# plotter_control.net
KiCad netlist of a schematic drawn in EAGLE
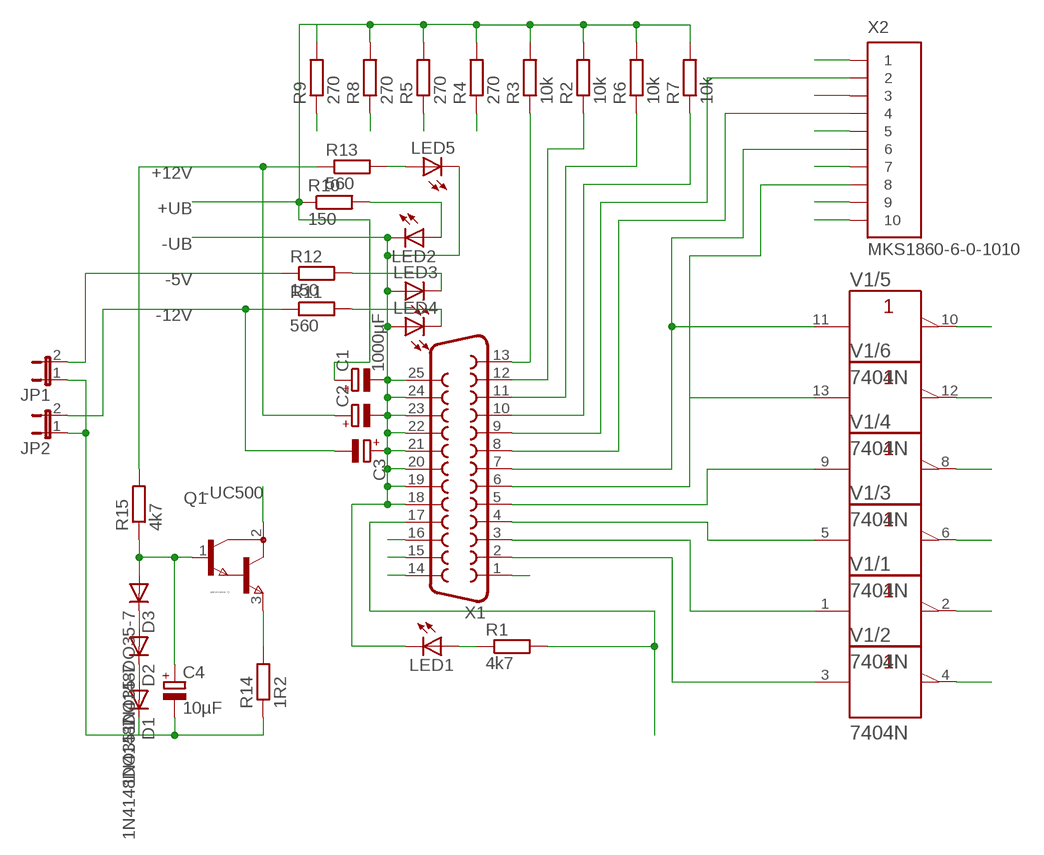
[diagram p0: schematic, sheet 1]

(export (version "E")
  (design (tool "Eeschema 10.0.6"))
  (components
    (comp (ref "C1")
      (value "1000µF")
      (footprint "eagle-import:E5-8,5")
      (libsource (lib "eagle-import") (part "CPOL-EUE5-8.5"))
    )
    (comp (ref "C2")
      (value "CPOL-EUE5-8.5")
      (footprint "eagle-import:E5-8,5")
      (libsource (lib "eagle-import") (part "CPOL-EUE5-8.5"))
    )
    (comp (ref "C3")
      (value "CPOL-EUE5-8.5")
      (footprint "eagle-import:E5-8,5")
      (libsource (lib "eagle-import") (part "CPOL-EUE5-8.5"))
    )
    (comp (ref "C4")
      (value "10µF")
      (footprint "eagle-import:E2,5-5")
      (libsource (lib "eagle-import") (part "CPOL-EUE2.5-5"))
    )
    (comp (ref "D1")
      (value "1N4148DO35-7")
      (footprint "eagle-import:DO35-7")
      (libsource (lib "eagle-import") (part "1N4148DO35-7"))
    )
    (comp (ref "D2")
      (value "1N4148DO35-7")
      (footprint "eagle-import:DO35-7")
      (libsource (lib "eagle-import") (part "1N4148DO35-7"))
    )
    (comp (ref "D3")
      (value "1N4148DO35-7")
      (footprint "eagle-import:DO35-7")
      (libsource (lib "eagle-import") (part "1N4148DO35-7"))
    )
    (comp (ref "JP1")
      (value "JP1E")
      (footprint "eagle-import:JP1")
      (libsource (lib "eagle-import") (part "JP1E"))
    )
    (comp (ref "JP2")
      (value "JP1E")
      (footprint "eagle-import:JP1")
      (libsource (lib "eagle-import") (part "JP1E"))
    )
    (comp (ref "LED1")
      (value "LED3MM")
      (footprint "eagle-import:LED3MM")
      (libsource (lib "eagle-import") (part "LED3MM"))
    )
    (comp (ref "LED2")
      (value "LED3MM")
      (footprint "eagle-import:LED3MM")
      (libsource (lib "eagle-import") (part "LED3MM"))
    )
    (comp (ref "LED3")
      (value "LED3MM")
      (footprint "eagle-import:LED3MM")
      (libsource (lib "eagle-import") (part "LED3MM"))
    )
    (comp (ref "LED4")
      (value "LED3MM")
      (footprint "eagle-import:LED3MM")
      (libsource (lib "eagle-import") (part "LED3MM"))
    )
    (comp (ref "LED5")
      (value "LED3MM")
      (footprint "eagle-import:LED3MM")
      (libsource (lib "eagle-import") (part "LED3MM"))
    )
    (comp (ref "Q1")
      (value "BD647")
      (footprint "eagle-import:TO220")
      (libsource (lib "eagle-import") (part "BD647"))
    )
    (comp (ref "R1")
      (value "4k7")
      (footprint "eagle-import:0204_7")
      (libsource (lib "eagle-import") (part "R-EU_0204/7"))
    )
    (comp (ref "R2")
      (value "10k")
      (footprint "eagle-import:0204_7")
      (libsource (lib "eagle-import") (part "R-EU_0204/7"))
    )
    (comp (ref "R3")
      (value "10k")
      (footprint "eagle-import:0204_7")
      (libsource (lib "eagle-import") (part "R-EU_0204/7"))
    )
    (comp (ref "R4")
      (value "270")
      (footprint "eagle-import:0204_7")
      (libsource (lib "eagle-import") (part "R-EU_0204/7"))
    )
    (comp (ref "R5")
      (value "270")
      (footprint "eagle-import:0204_7")
      (libsource (lib "eagle-import") (part "R-EU_0204/7"))
    )
    (comp (ref "R6")
      (value "10k")
      (footprint "eagle-import:0204_7")
      (libsource (lib "eagle-import") (part "R-EU_0204/7"))
    )
    (comp (ref "R7")
      (value "10k")
      (footprint "eagle-import:0204_7")
      (libsource (lib "eagle-import") (part "R-EU_0204/7"))
    )
    (comp (ref "R8")
      (value "270")
      (footprint "eagle-import:0204_7")
      (libsource (lib "eagle-import") (part "R-EU_0204/7"))
    )
    (comp (ref "R9")
      (value "270")
      (footprint "eagle-import:0204_7")
      (libsource (lib "eagle-import") (part "R-EU_0204/7"))
    )
    (comp (ref "R10")
      (value "150")
      (footprint "eagle-import:0207_15")
      (libsource (lib "eagle-import") (part "R-EU_0207/15"))
    )
    (comp (ref "R11")
      (value "560")
      (footprint "eagle-import:0204_7")
      (libsource (lib "eagle-import") (part "R-EU_0204/7"))
    )
    (comp (ref "R12")
      (value "150")
      (footprint "eagle-import:0207_10")
      (libsource (lib "eagle-import") (part "R-EU_0207/10"))
    )
    (comp (ref "R13")
      (value "560")
      (footprint "eagle-import:0204_7")
      (libsource (lib "eagle-import") (part "R-EU_0204/7"))
    )
    (comp (ref "R14")
      (value "1R2")
      (footprint "eagle-import:0204_7")
      (libsource (lib "eagle-import") (part "R-EU_0204/7"))
    )
    (comp (ref "R15")
      (value "4k7")
      (footprint "eagle-import:0204_7")
      (libsource (lib "eagle-import") (part "R-EU_0204/7"))
    )
    (comp (ref "V1")
      (value "7404N")
      (footprint "eagle-import:DIL14")
      (libsource (lib "eagle-import") (part "7404N"))
    )
    (comp (ref "X1")
      (value "F25HP")
      (footprint "eagle-import:F25HP")
      (libsource (lib "eagle-import") (part "F25HP"))
    )
    (comp (ref "X2")
      (value "MKS1860-6-0-1010")
      (footprint "eagle-import:MKS1860-6-0-1010")
      (libsource (lib "eagle-import") (part "MKS1860-6-0-1010"))
    )
  )
  (nets
    (net (code "1") (name "/+12V") (class "Default")
      (node (ref "C2") (pin "+") (pinfunction "+_+") (pintype "passive"))
      (node (ref "R13") (pin "1") (pinfunction "1_1") (pintype "passive"))
      (node (ref "R15") (pin "2") (pinfunction "2_2") (pintype "passive"))
    )
    (net (code "2") (name "/+UB") (class "Default")
      (node (ref "C1") (pin "+") (pinfunction "+_+") (pintype "passive"))
      (node (ref "R10") (pin "1") (pinfunction "1_1") (pintype "passive"))
      (node (ref "R2") (pin "2") (pinfunction "2_2") (pintype "passive"))
      (node (ref "R3") (pin "2") (pinfunction "2_2") (pintype "passive"))
      (node (ref "R4") (pin "2") (pinfunction "2_2") (pintype "passive"))
      (node (ref "R5") (pin "2") (pinfunction "2_2") (pintype "passive"))
      (node (ref "R6") (pin "2") (pinfunction "2_2") (pintype "passive"))
      (node (ref "R7") (pin "2") (pinfunction "2_2") (pintype "passive"))
      (node (ref "R8") (pin "2") (pinfunction "2_2") (pintype "passive"))
      (node (ref "R9") (pin "2") (pinfunction "2_2") (pintype "passive"))
    )
    (net (code "3") (name "/-5V") (class "Default")
      (node (ref "JP1") (pin "2") (pinfunction "2_2") (pintype "passive"))
      (node (ref "R12") (pin "1") (pinfunction "1_1") (pintype "passive"))
    )
    (net (code "4") (name "/-12V") (class "Default")
      (node (ref "C3") (pin "-") (pinfunction "-_-") (pintype "passive"))
      (node (ref "JP2") (pin "2") (pinfunction "2_2") (pintype "passive"))
      (node (ref "R11") (pin "1") (pinfunction "1_1") (pintype "passive"))
    )
    (net (code "5") (name "/-UB") (class "Default")
      (node (ref "C1") (pin "-") (pinfunction "-_-") (pintype "passive"))
      (node (ref "C2") (pin "-") (pinfunction "-_-") (pintype "passive"))
      (node (ref "C3") (pin "+") (pinfunction "+_+") (pintype "passive"))
      (node (ref "LED1") (pin "K") (pinfunction "C_K") (pintype "passive"))
      (node (ref "LED2") (pin "K") (pinfunction "C_K") (pintype "passive"))
      (node (ref "LED3") (pin "A") (pinfunction "A_A") (pintype "passive"))
      (node (ref "LED4") (pin "A") (pinfunction "A_A") (pintype "passive"))
      (node (ref "LED5") (pin "K") (pinfunction "C_K") (pintype "passive"))
      (node (ref "X1") (pin "18") (pinfunction "18_18") (pintype "passive"))
      (node (ref "X1") (pin "19") (pinfunction "19_19") (pintype "passive"))
      (node (ref "X1") (pin "20") (pinfunction "20_20") (pintype "passive"))
      (node (ref "X1") (pin "21") (pinfunction "21_21") (pintype "passive"))
      (node (ref "X1") (pin "22") (pinfunction "22_22") (pintype "passive"))
      (node (ref "X1") (pin "23") (pinfunction "23_23") (pintype "passive"))
      (node (ref "X1") (pin "24") (pinfunction "24_24") (pintype "passive"))
      (node (ref "X1") (pin "25") (pinfunction "25_25") (pintype "passive"))
      (node (ref "X2") (pin "1") (pinfunction "1_1") (pintype "input"))
      (node (ref "X2") (pin "10") (pinfunction "10_10") (pintype "input"))
    )
    (net (code "6") (name "/-UC500") (class "Default")
      (node (ref "Q1") (pin "2") (pinfunction "C_2") (pintype "passive"))
    )
    (net (code "7") (name "Net-(C4-Pad-)") (class "Default")
      (node (ref "C4") (pin "-") (pinfunction "-_-") (pintype "passive"))
      (node (ref "D1") (pin "C") (pinfunction "C_C") (pintype "passive"))
      (node (ref "JP1") (pin "1") (pinfunction "1_1") (pintype "passive"))
      (node (ref "JP2") (pin "1") (pinfunction "1_1") (pintype "passive"))
      (node (ref "R14") (pin "1") (pinfunction "1_1") (pintype "passive"))
    )
    (net (code "8") (name "Net-(D1-PadA)") (class "Default")
      (node (ref "D1") (pin "A") (pinfunction "A_A") (pintype "passive"))
      (node (ref "D2") (pin "C") (pinfunction "C_C") (pintype "passive"))
    )
    (net (code "9") (name "Net-(D2-PadA)") (class "Default")
      (node (ref "D2") (pin "A") (pinfunction "A_A") (pintype "passive"))
      (node (ref "D3") (pin "C") (pinfunction "C_C") (pintype "passive"))
    )
    (net (code "10") (name "Net-(LED1-PadA)") (class "Default")
      (node (ref "LED1") (pin "A") (pinfunction "A_A") (pintype "passive"))
      (node (ref "R1") (pin "1") (pinfunction "1_1") (pintype "passive"))
    )
    (net (code "11") (name "Net-(LED2-PadA)") (class "Default")
      (node (ref "LED2") (pin "A") (pinfunction "A_A") (pintype "passive"))
      (node (ref "R10") (pin "2") (pinfunction "2_2") (pintype "passive"))
    )
    (net (code "12") (name "Net-(LED3-C)") (class "Default")
      (node (ref "LED3") (pin "K") (pinfunction "C_K") (pintype "passive"))
      (node (ref "R12") (pin "2") (pinfunction "2_2") (pintype "passive"))
    )
    (net (code "13") (name "Net-(LED4-C)") (class "Default")
      (node (ref "LED4") (pin "K") (pinfunction "C_K") (pintype "passive"))
      (node (ref "R11") (pin "2") (pinfunction "2_2") (pintype "passive"))
    )
    (net (code "14") (name "Net-(LED5-PadA)") (class "Default")
      (node (ref "LED5") (pin "A") (pinfunction "A_A") (pintype "passive"))
      (node (ref "R13") (pin "2") (pinfunction "2_2") (pintype "passive"))
    )
    (net (code "15") (name "Net-(Q1-B)") (class "Default")
      (node (ref "C4") (pin "+") (pinfunction "+_+") (pintype "passive"))
      (node (ref "D3") (pin "A") (pinfunction "A_A") (pintype "passive"))
      (node (ref "Q1") (pin "1") (pinfunction "B_1") (pintype "passive"))
      (node (ref "R15") (pin "1") (pinfunction "1_1") (pintype "passive"))
    )
    (net (code "16") (name "Net-(Q1-E)") (class "Default")
      (node (ref "Q1") (pin "3") (pinfunction "E_3") (pintype "passive"))
      (node (ref "R14") (pin "2") (pinfunction "2_2") (pintype "passive"))
    )
    (net (code "17") (name "Net-(R1-Pad2)") (class "Default")
      (node (ref "R1") (pin "2") (pinfunction "2_2") (pintype "passive"))
      (node (ref "X1") (pin "17") (pinfunction "17_17") (pintype "passive"))
    )
    (net (code "18") (name "Net-(R2-Pad1)") (class "Default")
      (node (ref "R2") (pin "1") (pinfunction "1_1") (pintype "passive"))
      (node (ref "X1") (pin "12") (pinfunction "12_12") (pintype "passive"))
    )
    (net (code "19") (name "Net-(R3-Pad1)") (class "Default")
      (node (ref "R3") (pin "1") (pinfunction "1_1") (pintype "passive"))
      (node (ref "X1") (pin "13") (pinfunction "13_13") (pintype "passive"))
    )
    (net (code "20") (name "Net-(R6-Pad1)") (class "Default")
      (node (ref "R6") (pin "1") (pinfunction "1_1") (pintype "passive"))
      (node (ref "X1") (pin "11") (pinfunction "11_11") (pintype "passive"))
    )
    (net (code "21") (name "Net-(R7-Pad1)") (class "Default")
      (node (ref "R7") (pin "1") (pinfunction "1_1") (pintype "passive"))
      (node (ref "X1") (pin "10") (pinfunction "10_10") (pintype "passive"))
    )
    (net (code "22") (name "Net-(V1C-A)") (class "Default")
      (node (ref "V1") (pin "1") (pinfunction "A_1") (pintype "input"))
      (node (ref "X1") (pin "3") (pinfunction "3_3") (pintype "passive"))
    )
    (net (code "23") (name "Net-(V1D-A)") (class "Default")
      (node (ref "V1") (pin "3") (pinfunction "A_3") (pintype "input"))
      (node (ref "X1") (pin "2") (pinfunction "2_2") (pintype "passive"))
    )
    (net (code "24") (name "Net-(V1E-A)") (class "Default")
      (node (ref "V1") (pin "5") (pinfunction "A_5") (pintype "input"))
      (node (ref "X1") (pin "4") (pinfunction "4_4") (pintype "passive"))
    )
    (net (code "25") (name "Net-(V1F-A)") (class "Default")
      (node (ref "V1") (pin "9") (pinfunction "A_9") (pintype "input"))
      (node (ref "X1") (pin "5") (pinfunction "5_5") (pintype "passive"))
    )
    (net (code "26") (name "Net-(V1G-A)") (class "Default")
      (node (ref "V1") (pin "11") (pinfunction "A_11") (pintype "input"))
      (node (ref "X1") (pin "7") (pinfunction "7_7") (pintype "passive"))
      (node (ref "X2") (pin "6") (pinfunction "6_6") (pintype "input"))
    )
    (net (code "27") (name "Net-(V1H-A)") (class "Default")
      (node (ref "V1") (pin "13") (pinfunction "A_13") (pintype "input"))
      (node (ref "X1") (pin "6") (pinfunction "6_6") (pintype "passive"))
      (node (ref "X2") (pin "8") (pinfunction "8_8") (pintype "input"))
    )
    (net (code "28") (name "Net-(X1-Pad8)") (class "Default")
      (node (ref "X1") (pin "8") (pinfunction "8_8") (pintype "passive"))
      (node (ref "X2") (pin "4") (pinfunction "4_4") (pintype "input"))
    )
    (net (code "29") (name "Net-(X1-Pad9)") (class "Default")
      (node (ref "X1") (pin "9") (pinfunction "9_9") (pintype "passive"))
      (node (ref "X2") (pin "2") (pinfunction "2_2") (pintype "input"))
    )
    (net (code "30") (name "unconnected-(R4-Pad1)") (class "Default")
      (node (ref "R4") (pin "1") (pinfunction "1_1") (pintype "passive"))
    )
    (net (code "31") (name "unconnected-(R5-Pad1)") (class "Default")
      (node (ref "R5") (pin "1") (pinfunction "1_1") (pintype "passive"))
    )
    (net (code "32") (name "unconnected-(R8-Pad1)") (class "Default")
      (node (ref "R8") (pin "1") (pinfunction "1_1") (pintype "passive"))
    )
    (net (code "33") (name "unconnected-(R9-Pad1)") (class "Default")
      (node (ref "R9") (pin "1") (pinfunction "1_1") (pintype "passive"))
    )
    (net (code "34") (name "unconnected-(V1C-Y-Pad2)") (class "Default")
      (node (ref "V1") (pin "2") (pinfunction "Y_2") (pintype "output"))
    )
    (net (code "35") (name "unconnected-(V1D-Y-Pad4)") (class "Default")
      (node (ref "V1") (pin "4") (pinfunction "Y_4") (pintype "output"))
    )
    (net (code "36") (name "unconnected-(V1E-Y-Pad6)") (class "Default")
      (node (ref "V1") (pin "6") (pinfunction "Y_6") (pintype "output"))
    )
    (net (code "37") (name "unconnected-(V1F-Y-Pad8)") (class "Default")
      (node (ref "V1") (pin "8") (pinfunction "Y_8") (pintype "output"))
    )
    (net (code "38") (name "unconnected-(V1G-Y-Pad10)") (class "Default")
      (node (ref "V1") (pin "10") (pinfunction "Y_10") (pintype "output"))
    )
    (net (code "39") (name "unconnected-(V1H-Y-Pad12)") (class "Default")
      (node (ref "V1") (pin "12") (pinfunction "Y_12") (pintype "output"))
    )
    (net (code "40") (name "unconnected-(X1-Pad1)") (class "Default")
      (node (ref "X1") (pin "1") (pinfunction "1_1") (pintype "passive"))
    )
    (net (code "41") (name "unconnected-(X1-Pad14)") (class "Default")
      (node (ref "X1") (pin "14") (pinfunction "14_14") (pintype "passive"))
    )
    (net (code "42") (name "unconnected-(X1-Pad15)") (class "Default")
      (node (ref "X1") (pin "15") (pinfunction "15_15") (pintype "passive"))
    )
    (net (code "43") (name "unconnected-(X1-Pad16)") (class "Default")
      (node (ref "X1") (pin "16") (pinfunction "16_16") (pintype "passive"))
    )
    (net (code "44") (name "unconnected-(X2-Pad3)") (class "Default")
      (node (ref "X2") (pin "3") (pinfunction "3_3") (pintype "input"))
    )
    (net (code "45") (name "unconnected-(X2-Pad5)") (class "Default")
      (node (ref "X2") (pin "5") (pinfunction "5_5") (pintype "input"))
    )
    (net (code "46") (name "unconnected-(X2-Pad7)") (class "Default")
      (node (ref "X2") (pin "7") (pinfunction "7_7") (pintype "input"))
    )
    (net (code "47") (name "unconnected-(X2-Pad9)") (class "Default")
      (node (ref "X2") (pin "9") (pinfunction "9_9") (pintype "input"))
    )
  )
)
